# PhatStats_Slim_Enclosure_ESP_Lolin32_LIT.net
KiCad netlist of a schematic drawn in EAGLE
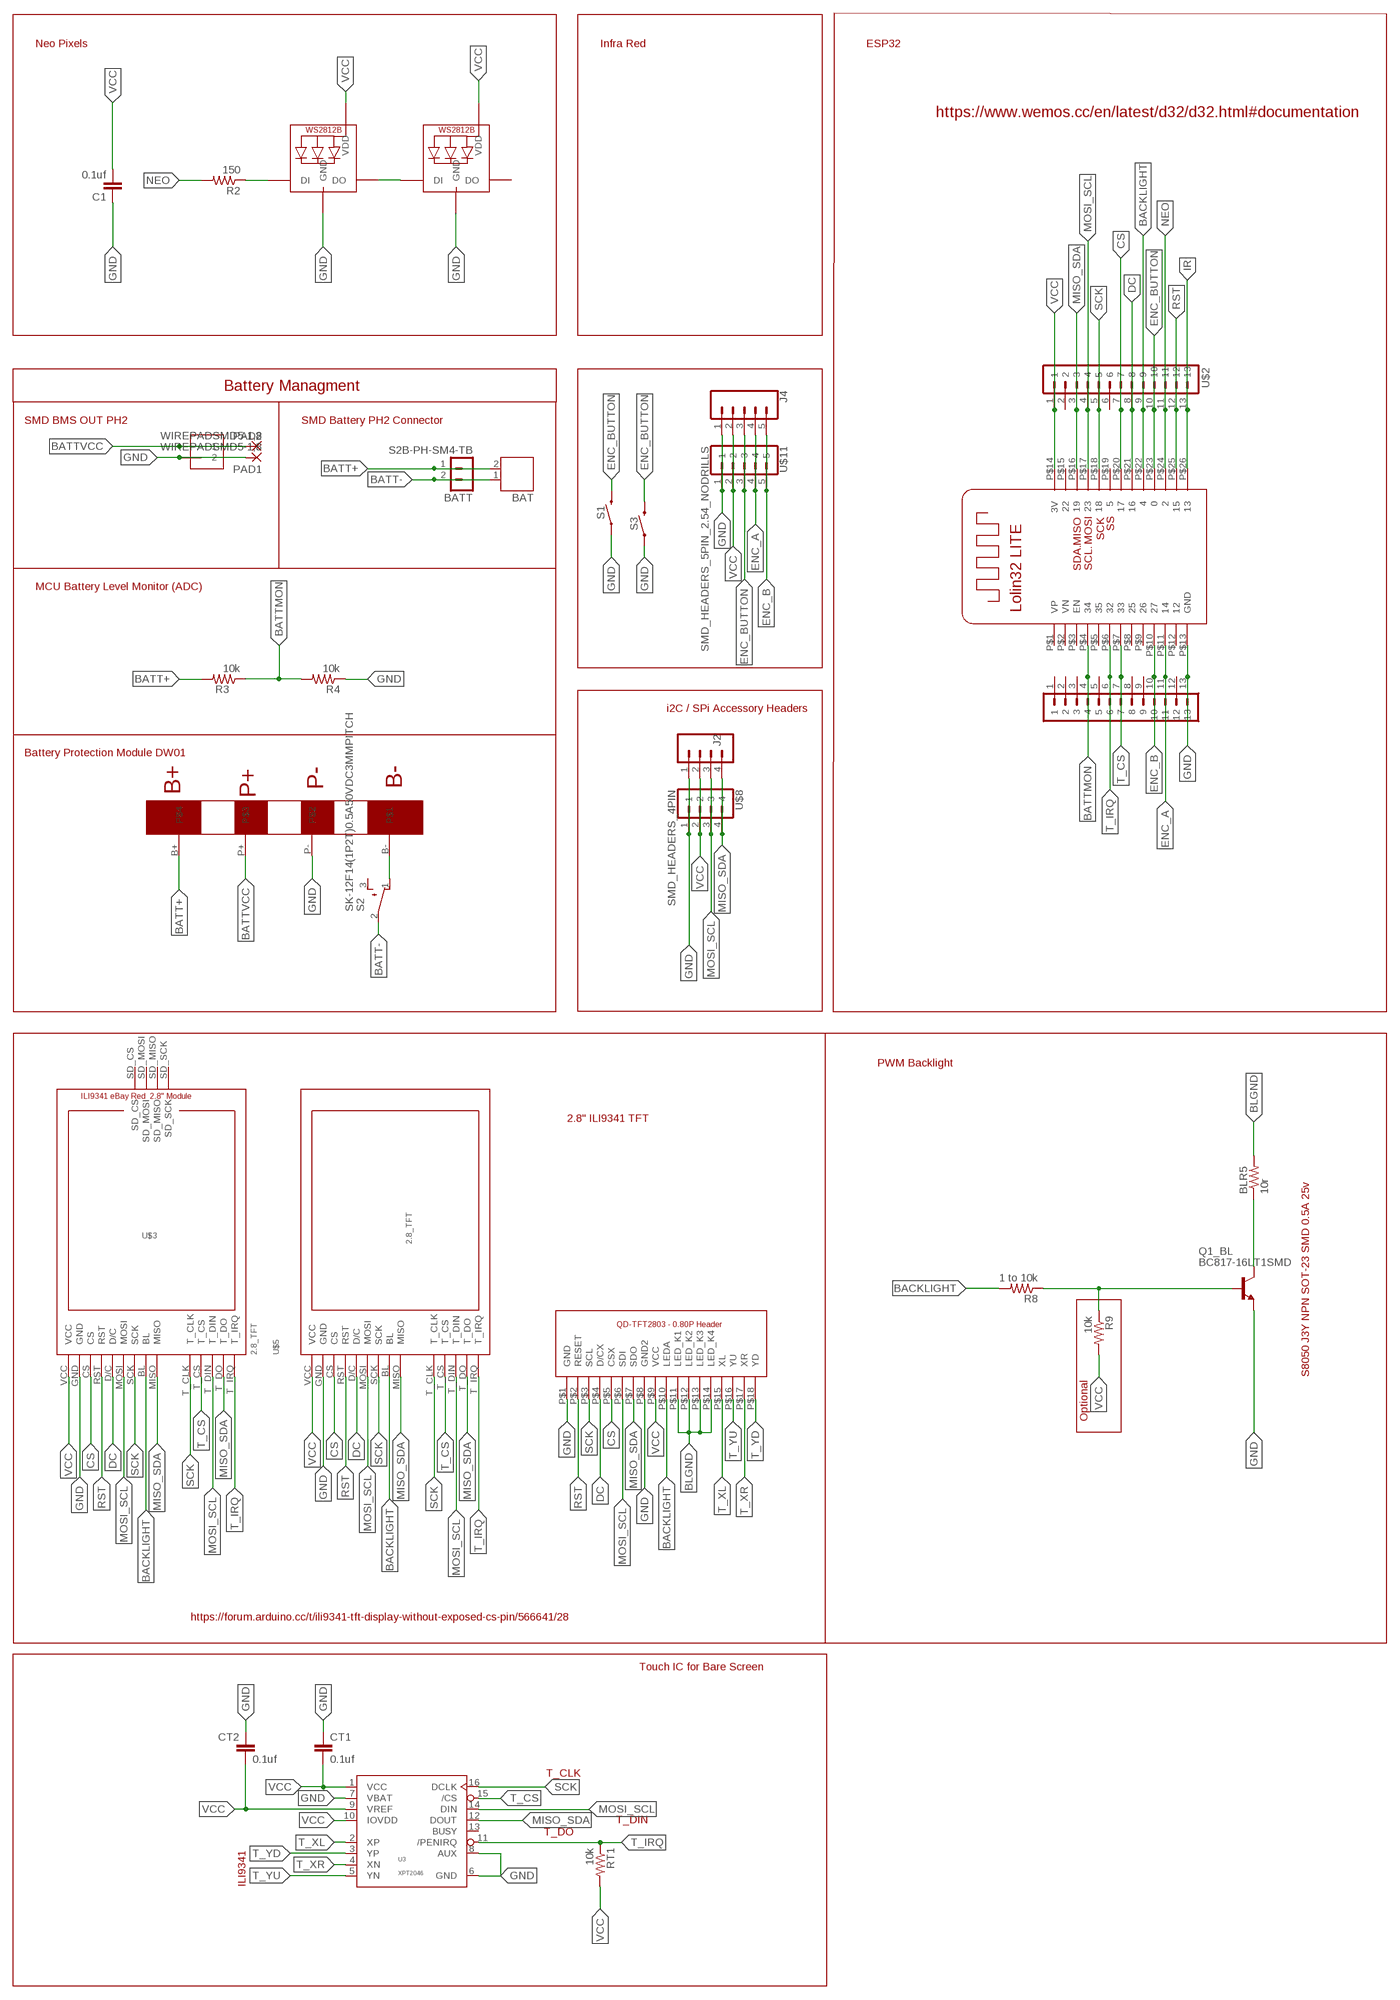
[diagram p0: schematic, sheet 1]

(export (version "E")
  (design (tool "Eeschema 10.0.6"))
  (components
    (comp (ref "0")
      (value "ILI9341-2.8")
      (footprint "eagle-import:ILI9341-2.8")
      (libsource (lib "eagle-import") (part "ILI9341-2.8"))
    )
    (comp (ref "BAT")
      (value "JST-PH2")
      (footprint "eagle-import:JST-PH2")
      (libsource (lib "eagle-import") (part "JST-PH2"))
    )
    (comp (ref "BATT")
      (value "S2B-PH-SM4-TB")
      (footprint "eagle-import:S2B-PH-SM4-TB")
      (libsource (lib "eagle-import") (part "S2B-PH-SM4-TB"))
    )
    (comp (ref "BLR5")
      (value "10r")
      (footprint "eagle-import:M1206")
      (libsource (lib "eagle-import") (part "R-US_M1206"))
    )
    (comp (ref "C1")
      (value "0.1uf")
      (footprint "eagle-import:C1206")
      (libsource (lib "eagle-import") (part "C-EUC1206"))
    )
    (comp (ref "CT1")
      (value "0.1uf")
      (footprint "eagle-import:C1206")
      (libsource (lib "eagle-import") (part "C-EUC1206"))
    )
    (comp (ref "CT2")
      (value "0.1uf")
      (footprint "eagle-import:C1206")
      (libsource (lib "eagle-import") (part "C-EUC1206"))
    )
    (comp (ref "DW01-BMS")
      (value "DW01BATTERYPROT")
      (footprint "eagle-import:DW01BATTERYPROT")
      (libsource (lib "eagle-import") (part "DW01BATTERYPROT"))
    )
    (comp (ref "J1")
      (value "1X2-3.5MM")
      (footprint "eagle-import:1X2-3.5MM")
      (libsource (lib "eagle-import") (part "1X2-3.5MM"))
    )
    (comp (ref "J2")
      (value "CONN_04PTH")
      (footprint "eagle-import:1X04")
      (libsource (lib "eagle-import") (part "CONN_04PTH"))
    )
    (comp (ref "J4")
      (value "CONN_05")
      (footprint "eagle-import:1X05")
      (libsource (lib "eagle-import") (part "CONN_05"))
    )
    (comp (ref "NEO0")
      (value "WS2812B5050")
      (footprint "eagle-import:WS2812B")
      (libsource (lib "eagle-import") (part "WS2812B5050"))
    )
    (comp (ref "NEO1")
      (value "WS2812B5050")
      (footprint "eagle-import:WS2812B")
      (libsource (lib "eagle-import") (part "WS2812B5050"))
    )
    (comp (ref "PAD1")
      (value "WIREPADSMD5-1,8")
      (footprint "eagle-import:5-1,8")
      (libsource (lib "eagle-import") (part "WIREPADSMD5-1,8"))
    )
    (comp (ref "PAD2")
      (value "WIREPADSMD5-1,8")
      (footprint "eagle-import:5-1,8")
      (libsource (lib "eagle-import") (part "WIREPADSMD5-1,8"))
    )
    (comp (ref "Q1_BL")
      (value "BC817-16LT1SMD")
      (footprint "eagle-import:SOT23-BEC")
      (libsource (lib "eagle-import") (part "BC817SMD-16LT1"))
    )
    (comp (ref "R2")
      (value "150")
      (footprint "eagle-import:M1206")
      (libsource (lib "eagle-import") (part "R-US_M1206"))
    )
    (comp (ref "R3")
      (value "10k")
      (footprint "eagle-import:M1206")
      (libsource (lib "eagle-import") (part "R-US_M1206"))
    )
    (comp (ref "R4")
      (value "10k")
      (footprint "eagle-import:M1206")
      (libsource (lib "eagle-import") (part "R-US_M1206"))
    )
    (comp (ref "R8")
      (value "1 to 10k")
      (footprint "eagle-import:M1206")
      (libsource (lib "eagle-import") (part "R-US_M1206"))
    )
    (comp (ref "R9")
      (value "10k")
      (footprint "eagle-import:M1206")
      (libsource (lib "eagle-import") (part "R-US_M1206"))
    )
    (comp (ref "RT1")
      (value "10k")
      (footprint "eagle-import:M1206")
      (libsource (lib "eagle-import") (part "R-US_M1206"))
    )
    (comp (ref "S1")
      (value "MOMENTARY-SWITCH-SPST-PTH-6.0MM")
      (footprint "eagle-import:TACTILE_SWITCH_PTH_6.0MM")
      (libsource (lib "eagle-import") (part "MOMENTARY-SWITCH-SPST-PTH-6.0MM"))
    )
    (comp (ref "S2")
      (value "SK-12F14(1P2T)0.5A50VDC3MMPITCH")
      (footprint "eagle-import:SK-12F14(1P2T)0.5A50VDC3MMPITCH")
      (libsource (lib "eagle-import") (part "SK-12F14(1P2T)0.5A50VDC3MMPITCH"))
    )
    (comp (ref "S3")
      (value "MOMENTARY-SWITCH-SPST-SMD-6.2MM-TALL")
      (footprint "eagle-import:TACTILE_SWITCH_SMD_6.2MM_TALL")
      (libsource (lib "eagle-import") (part "MOMENTARY-SWITCH-SPST-SMD-6.2MM-TALL"))
    )
    (comp (ref "U$1")
      (value "SMD_HEADERS_13PIN_2.54_NODRILLS")
      (footprint "eagle-import:SMD_HEADERS_13PIN")
      (libsource (lib "eagle-import") (part "SMD_HEADERS_13PIN_2.54_NODRILLS"))
    )
    (comp (ref "U$2")
      (value "SMD_HEADERS_13PIN_2.54_NODRILLS")
      (footprint "eagle-import:SMD_HEADERS_13PIN")
      (libsource (lib "eagle-import") (part "SMD_HEADERS_13PIN_2.54_NODRILLS"))
    )
    (comp (ref "U$3")
      (value "2.8_TFT")
      (footprint "eagle-import:2.8_TFT")
      (libsource (lib "eagle-import") (part "2.8_TFT"))
    )
    (comp (ref "U$5")
      (value "2.8_TFT")
      (footprint "eagle-import:2.8_TFT")
      (libsource (lib "eagle-import") (part "TML_ili9341-2.8_tft-display_PinHeader only_2.8_TFT"))
    )
    (comp (ref "U$7")
      (value "TML_LOLIND32_LITE")
      (footprint "eagle-import:TML_LOLIND32_LITE")
      (libsource (lib "eagle-import") (part "TML_LOLIND32_LITE"))
    )
    (comp (ref "U$8")
      (value "SMD_HEADERS_4PIN")
      (footprint "eagle-import:SMD_HEADERS_4PIN")
      (libsource (lib "eagle-import") (part "SMD_HEADERS_4PIN"))
    )
    (comp (ref "U$11")
      (value "SMD_HEADERS_5PIN_2.54_NODRILLS")
      (footprint "eagle-import:SMD_HEADERS_5PIN")
      (libsource (lib "eagle-import") (part "SMD_HEADERS_5PIN_2.54_NODRILLS"))
    )
    (comp (ref "U3")
      (value "XPT2046")
      (footprint "eagle-import:TSSOP-16")
      (fields (field (name "MF") "Xptek"))
      (libsource (lib "eagle-import") (part "XPT2046"))
    )
  )
  (nets
    (net (code "1") (name "BACKLIGHT") (class "Default")
      (node (ref "0") (pin "P$10") (pinfunction "LEDA_P$10") (pintype "bidirectional"))
      (node (ref "R8") (pin "2") (pinfunction "2_2") (pintype "passive"))
      (node (ref "U$2") (pin "9") (pinfunction "9_9") (pintype "bidirectional"))
      (node (ref "U$3") (pin "BL") (pinfunction "BL_BL") (pintype "bidirectional"))
      (node (ref "U$5") (pin "BL") (pinfunction "BL_BL") (pintype "bidirectional"))
      (node (ref "U$7") (pin "P$22") (pinfunction "4_P$22") (pintype "bidirectional"))
    )
    (net (code "2") (name "BATT+") (class "Default")
      (node (ref "BAT") (pin "2") (pinfunction "2_2") (pintype "passive"))
      (node (ref "BATT") (pin "1") (pinfunction "1_1") (pintype "passive"))
      (node (ref "DW01-BMS") (pin "B+") (pinfunction "P$4_B+") (pintype "bidirectional"))
      (node (ref "R3") (pin "2") (pinfunction "2_2") (pintype "passive"))
    )
    (net (code "3") (name "BATT-") (class "Default")
      (node (ref "BAT") (pin "1") (pinfunction "1_1") (pintype "passive"))
      (node (ref "BATT") (pin "2") (pinfunction "2_2") (pintype "passive"))
      (node (ref "S2") (pin "2") (pinfunction "P_2") (pintype "passive"))
    )
    (net (code "4") (name "BATTMON") (class "Default")
      (node (ref "R3") (pin "1") (pinfunction "1_1") (pintype "passive"))
      (node (ref "R4") (pin "2") (pinfunction "2_2") (pintype "passive"))
      (node (ref "U$1") (pin "4") (pinfunction "4_4") (pintype "bidirectional"))
      (node (ref "U$7") (pin "P$4") (pinfunction "34_P$4") (pintype "bidirectional"))
    )
    (net (code "5") (name "BATTVCC") (class "Default")
      (node (ref "DW01-BMS") (pin "P+") (pinfunction "P$3_P+") (pintype "bidirectional"))
      (node (ref "J1") (pin "1") (pinfunction "1_1") (pintype "passive"))
      (node (ref "PAD2") (pin "1") (pinfunction "P_1") (pintype "passive"))
    )
    (net (code "6") (name "BLGND") (class "Default")
      (node (ref "0") (pin "P$11") (pinfunction "LED_K1_P$11") (pintype "bidirectional"))
      (node (ref "0") (pin "P$12") (pinfunction "LED_K2_P$12") (pintype "bidirectional"))
      (node (ref "0") (pin "P$13") (pinfunction "LED_K3_P$13") (pintype "bidirectional"))
      (node (ref "0") (pin "P$14") (pinfunction "LED_K4_P$14") (pintype "bidirectional"))
      (node (ref "BLR5") (pin "2") (pinfunction "2_2") (pintype "passive"))
    )
    (net (code "7") (name "CS") (class "Default")
      (node (ref "0") (pin "P$5") (pinfunction "CSX_P$5") (pintype "bidirectional"))
      (node (ref "U$2") (pin "7") (pinfunction "7_7") (pintype "bidirectional"))
      (node (ref "U$3") (pin "CS") (pinfunction "CS_CS") (pintype "bidirectional"))
      (node (ref "U$5") (pin "CS") (pinfunction "CS_CS") (pintype "bidirectional"))
      (node (ref "U$7") (pin "P$20") (pinfunction "17_P$20") (pintype "bidirectional"))
    )
    (net (code "8") (name "DC") (class "Default")
      (node (ref "0") (pin "P$4") (pinfunction "D/CX_P$4") (pintype "bidirectional"))
      (node (ref "U$2") (pin "8") (pinfunction "8_8") (pintype "bidirectional"))
      (node (ref "U$3") (pin "D/C") (pinfunction "D/C_D/C") (pintype "bidirectional"))
      (node (ref "U$5") (pin "D/C") (pinfunction "D/C_D/C") (pintype "bidirectional"))
      (node (ref "U$7") (pin "P$21") (pinfunction "16_P$21") (pintype "bidirectional"))
    )
    (net (code "9") (name "ENC_A") (class "Default")
      (node (ref "J4") (pin "4") (pinfunction "4_4") (pintype "passive"))
      (node (ref "U$1") (pin "11") (pinfunction "11_11") (pintype "bidirectional"))
      (node (ref "U$11") (pin "4") (pinfunction "4_4") (pintype "passive"))
      (node (ref "U$7") (pin "P$11") (pinfunction "14_P$11") (pintype "bidirectional"))
    )
    (net (code "10") (name "ENC_B") (class "Default")
      (node (ref "J4") (pin "5") (pinfunction "5_5") (pintype "passive"))
      (node (ref "U$1") (pin "10") (pinfunction "10_10") (pintype "bidirectional"))
      (node (ref "U$11") (pin "5") (pinfunction "5_5") (pintype "passive"))
      (node (ref "U$7") (pin "P$10") (pinfunction "27_P$10") (pintype "bidirectional"))
    )
    (net (code "11") (name "ENC_BUTTON") (class "Default")
      (node (ref "J4") (pin "3") (pinfunction "3_3") (pintype "passive"))
      (node (ref "S1") (pin "3") (pinfunction "2_3") (pintype "passive"))
      (node (ref "S3") (pin "B2") (pinfunction "2_B2") (pintype "passive"))
      (node (ref "U$11") (pin "3") (pinfunction "3_3") (pintype "passive"))
      (node (ref "U$2") (pin "10") (pinfunction "10_10") (pintype "bidirectional"))
      (node (ref "U$7") (pin "P$23") (pinfunction "0_P$23") (pintype "bidirectional"))
    )
    (net (code "12") (name "GND") (class "Default")
      (node (ref "0") (pin "P$1") (pinfunction "GND_P$1") (pintype "bidirectional"))
      (node (ref "0") (pin "P$8") (pinfunction "GND2_P$8") (pintype "bidirectional"))
      (node (ref "C1") (pin "1") (pinfunction "1_1") (pintype "passive"))
      (node (ref "CT1") (pin "1") (pinfunction "1_1") (pintype "passive"))
      (node (ref "CT2") (pin "1") (pinfunction "1_1") (pintype "passive"))
      (node (ref "DW01-BMS") (pin "P-") (pinfunction "P$2_P-") (pintype "bidirectional"))
      (node (ref "J1") (pin "2") (pinfunction "2_2") (pintype "passive"))
      (node (ref "J2") (pin "1") (pinfunction "1_1") (pintype "passive"))
      (node (ref "J4") (pin "1") (pinfunction "1_1") (pintype "passive"))
      (node (ref "NEO0") (pin "3-GND") (pinfunction "GND_3-GND") (pintype "power_in"))
      (node (ref "NEO1") (pin "3-GND") (pinfunction "GND_3-GND") (pintype "power_in"))
      (node (ref "PAD1") (pin "1") (pinfunction "P_1") (pintype "passive"))
      (node (ref "Q1_BL") (pin "E") (pinfunction "E_E") (pintype "passive"))
      (node (ref "R4") (pin "1") (pinfunction "1_1") (pintype "passive"))
      (node (ref "S1") (pin "1") (pinfunction "1_1") (pintype "passive"))
      (node (ref "S3") (pin "A2") (pinfunction "1_A2") (pintype "passive"))
      (node (ref "U$1") (pin "13") (pinfunction "13_13") (pintype "bidirectional"))
      (node (ref "U$11") (pin "1") (pinfunction "1_1") (pintype "passive"))
      (node (ref "U$3") (pin "GND") (pinfunction "GND_GND") (pintype "bidirectional"))
      (node (ref "U$5") (pin "GND") (pinfunction "GND_GND") (pintype "bidirectional"))
      (node (ref "U$7") (pin "P$13") (pinfunction "GND_P$13") (pintype "input"))
      (node (ref "U$8") (pin "1") (pinfunction "1_1") (pintype "passive"))
      (node (ref "U3") (pin "6") (pinfunction "GND_6") (pintype "power_in"))
      (node (ref "U3") (pin "7") (pinfunction "VBAT_7") (pintype "input"))
      (node (ref "U3") (pin "8") (pinfunction "AUX_8") (pintype "input"))
    )
    (net (code "13") (name "IR") (class "Default")
      (node (ref "U$2") (pin "13") (pinfunction "13_13") (pintype "bidirectional"))
      (node (ref "U$7") (pin "P$26") (pinfunction "13_P$26") (pintype "bidirectional"))
    )
    (net (code "14") (name "MISO_SDA") (class "Default")
      (node (ref "0") (pin "P$7") (pinfunction "SDO_P$7") (pintype "bidirectional"))
      (node (ref "J2") (pin "4") (pinfunction "4_4") (pintype "passive"))
      (node (ref "U$2") (pin "3") (pinfunction "3_3") (pintype "bidirectional"))
      (node (ref "U$3") (pin "MISO") (pinfunction "MISO_MISO") (pintype "bidirectional"))
      (node (ref "U$3") (pin "T_DO") (pinfunction "T_DO_T_DO") (pintype "bidirectional"))
      (node (ref "U$5") (pin "MISO") (pinfunction "MISO_MISO") (pintype "bidirectional"))
      (node (ref "U$5") (pin "T_DO") (pinfunction "T_DO_T_DO") (pintype "bidirectional"))
      (node (ref "U$7") (pin "P$16") (pinfunction "19_P$16") (pintype "bidirectional"))
      (node (ref "U$8") (pin "4") (pinfunction "4_4") (pintype "passive"))
      (node (ref "U3") (pin "12") (pinfunction "DOUT_12") (pintype "output"))
    )
    (net (code "15") (name "MOSI_SCL") (class "Default")
      (node (ref "0") (pin "P$6") (pinfunction "SDI_P$6") (pintype "bidirectional"))
      (node (ref "J2") (pin "3") (pinfunction "3_3") (pintype "passive"))
      (node (ref "U$2") (pin "4") (pinfunction "4_4") (pintype "bidirectional"))
      (node (ref "U$3") (pin "MOSI") (pinfunction "MOSI_MOSI") (pintype "bidirectional"))
      (node (ref "U$3") (pin "T_DIN") (pinfunction "T_DIN_T_DIN") (pintype "bidirectional"))
      (node (ref "U$5") (pin "MOSI") (pinfunction "MOSI_MOSI") (pintype "bidirectional"))
      (node (ref "U$5") (pin "T_DIN") (pinfunction "T_DIN_T_DIN") (pintype "bidirectional"))
      (node (ref "U$7") (pin "P$17") (pinfunction "23_P$17") (pintype "bidirectional"))
      (node (ref "U$8") (pin "3") (pinfunction "3_3") (pintype "passive"))
      (node (ref "U3") (pin "14") (pinfunction "DIN_14") (pintype "input"))
    )
    (net (code "16") (name "NEO") (class "Default")
      (node (ref "R2") (pin "2") (pinfunction "2_2") (pintype "passive"))
      (node (ref "U$2") (pin "11") (pinfunction "11_11") (pintype "bidirectional"))
      (node (ref "U$7") (pin "P$24") (pinfunction "2_P$24") (pintype "bidirectional"))
    )
    (net (code "17") (name "Net-(BLR5-Pad1)") (class "Default")
      (node (ref "BLR5") (pin "1") (pinfunction "1_1") (pintype "passive"))
      (node (ref "Q1_BL") (pin "C") (pinfunction "C_C") (pintype "passive"))
    )
    (net (code "18") (name "Net-(DW01-BMS-P$1)") (class "Default")
      (node (ref "DW01-BMS") (pin "B-") (pinfunction "P$1_B-") (pintype "bidirectional"))
      (node (ref "S2") (pin "1") (pinfunction "O_1") (pintype "passive"))
    )
    (net (code "19") (name "Net-(NEO0-DI)") (class "Default")
      (node (ref "NEO0") (pin "4-DIN") (pinfunction "DI_4-DIN") (pintype "input"))
      (node (ref "R2") (pin "1") (pinfunction "1_1") (pintype "passive"))
    )
    (net (code "20") (name "Net-(NEO0-DO)") (class "Default")
      (node (ref "NEO0") (pin "2-DOUT") (pinfunction "DO_2-DOUT") (pintype "output"))
      (node (ref "NEO1") (pin "4-DIN") (pinfunction "DI_4-DIN") (pintype "input"))
    )
    (net (code "21") (name "Net-(Q1_BL-PadB)") (class "Default")
      (node (ref "Q1_BL") (pin "B") (pinfunction "B_B") (pintype "passive"))
      (node (ref "R8") (pin "1") (pinfunction "1_1") (pintype "passive"))
      (node (ref "R9") (pin "1") (pinfunction "1_1") (pintype "passive"))
    )
    (net (code "22") (name "RST") (class "Default")
      (node (ref "0") (pin "P$2") (pinfunction "RESET_P$2") (pintype "bidirectional"))
      (node (ref "U$2") (pin "12") (pinfunction "12_12") (pintype "bidirectional"))
      (node (ref "U$3") (pin "RST") (pinfunction "RST_RST") (pintype "bidirectional"))
      (node (ref "U$5") (pin "RST") (pinfunction "RST_RST") (pintype "bidirectional"))
      (node (ref "U$7") (pin "P$25") (pinfunction "15_P$25") (pintype "bidirectional"))
    )
    (net (code "23") (name "SCK") (class "Default")
      (node (ref "0") (pin "P$3") (pinfunction "SCL_P$3") (pintype "bidirectional"))
      (node (ref "U$2") (pin "5") (pinfunction "5_5") (pintype "bidirectional"))
      (node (ref "U$3") (pin "SCK") (pinfunction "SCK_SCK") (pintype "bidirectional"))
      (node (ref "U$3") (pin "T_CLK") (pinfunction "T_CLK_T_CLK") (pintype "bidirectional"))
      (node (ref "U$5") (pin "SCK") (pinfunction "SCK_SCK") (pintype "bidirectional"))
      (node (ref "U$5") (pin "T_CLK") (pinfunction "T_CLK_T_CLK") (pintype "bidirectional"))
      (node (ref "U$7") (pin "P$18") (pinfunction "18_P$18") (pintype "bidirectional"))
      (node (ref "U3") (pin "16") (pinfunction "DCLK_16") (pintype "input"))
    )
    (net (code "24") (name "T_CS") (class "Default")
      (node (ref "U$1") (pin "7") (pinfunction "7_7") (pintype "bidirectional"))
      (node (ref "U$3") (pin "T_CS") (pinfunction "T_CS_T_CS") (pintype "bidirectional"))
      (node (ref "U$5") (pin "T_CS") (pinfunction "T_CS_T_CS") (pintype "bidirectional"))
      (node (ref "U$7") (pin "P$7") (pinfunction "33_P$7") (pintype "bidirectional"))
      (node (ref "U3") (pin "15") (pinfunction "/CS_15") (pintype "input"))
    )
    (net (code "25") (name "T_IRQ") (class "Default")
      (node (ref "RT1") (pin "1") (pinfunction "1_1") (pintype "passive"))
      (node (ref "U$1") (pin "6") (pinfunction "6_6") (pintype "bidirectional"))
      (node (ref "U$3") (pin "T_IRQ") (pinfunction "T_IRQ_T_IRQ") (pintype "bidirectional"))
      (node (ref "U$5") (pin "T_IRQ") (pinfunction "T_IRQ_T_IRQ") (pintype "bidirectional"))
      (node (ref "U$7") (pin "P$6") (pinfunction "32_P$6") (pintype "bidirectional"))
      (node (ref "U3") (pin "11") (pinfunction "/PENIRQ_11") (pintype "output"))
    )
    (net (code "26") (name "T_XL") (class "Default")
      (node (ref "0") (pin "P$15") (pinfunction "XL_P$15") (pintype "bidirectional"))
      (node (ref "U3") (pin "2") (pinfunction "XP_2") (pintype "input"))
    )
    (net (code "27") (name "T_XR") (class "Default")
      (node (ref "0") (pin "P$17") (pinfunction "XR_P$17") (pintype "bidirectional"))
      (node (ref "U3") (pin "4") (pinfunction "XN_4") (pintype "input"))
    )
    (net (code "28") (name "T_YD") (class "Default")
      (node (ref "0") (pin "P$18") (pinfunction "YD_P$18") (pintype "bidirectional"))
      (node (ref "U3") (pin "3") (pinfunction "YP_3") (pintype "input"))
    )
    (net (code "29") (name "T_YU") (class "Default")
      (node (ref "0") (pin "P$16") (pinfunction "YU_P$16") (pintype "bidirectional"))
      (node (ref "U3") (pin "5") (pinfunction "YN_5") (pintype "input"))
    )
    (net (code "30") (name "VCC") (class "Default")
      (node (ref "0") (pin "P$9") (pinfunction "VCC_P$9") (pintype "bidirectional"))
      (node (ref "C1") (pin "2") (pinfunction "2_2") (pintype "passive"))
      (node (ref "CT1") (pin "2") (pinfunction "2_2") (pintype "passive"))
      (node (ref "CT2") (pin "2") (pinfunction "2_2") (pintype "passive"))
      (node (ref "J2") (pin "2") (pinfunction "2_2") (pintype "passive"))
      (node (ref "J4") (pin "2") (pinfunction "2_2") (pintype "passive"))
      (node (ref "NEO0") (pin "1-VDD") (pinfunction "VDD_1-VDD") (pintype "power_in"))
      (node (ref "NEO1") (pin "1-VDD") (pinfunction "VDD_1-VDD") (pintype "power_in"))
      (node (ref "R9") (pin "2") (pinfunction "2_2") (pintype "passive"))
      (node (ref "RT1") (pin "2") (pinfunction "2_2") (pintype "passive"))
      (node (ref "U$11") (pin "2") (pinfunction "2_2") (pintype "passive"))
      (node (ref "U$2") (pin "1") (pinfunction "1_1") (pintype "bidirectional"))
      (node (ref "U$3") (pin "VCC") (pinfunction "VCC_VCC") (pintype "bidirectional"))
      (node (ref "U$5") (pin "VCC") (pinfunction "VCC_VCC") (pintype "bidirectional"))
      (node (ref "U$7") (pin "P$14") (pinfunction "3V_P$14") (pintype "input"))
      (node (ref "U$8") (pin "2") (pinfunction "2_2") (pintype "passive"))
      (node (ref "U3") (pin "1") (pinfunction "VCC_1") (pintype "power_in"))
      (node (ref "U3") (pin "10") (pinfunction "IOVDD_10") (pintype "power_in"))
      (node (ref "U3") (pin "9") (pinfunction "VREF_9") (pintype "input"))
    )
    (net (code "31") (name "unconnected-(NEO1-DO-Pad2-DOUT)") (class "Default")
      (node (ref "NEO1") (pin "2-DOUT") (pinfunction "DO_2-DOUT") (pintype "output"))
    )
    (net (code "32") (name "unconnected-(S2-S-Pad3)") (class "Default")
      (node (ref "S2") (pin "3") (pinfunction "S_3") (pintype "passive"))
    )
    (net (code "33") (name "unconnected-(U$1-Pad1)") (class "Default")
      (node (ref "U$1") (pin "1") (pinfunction "1_1") (pintype "bidirectional"))
    )
    (net (code "34") (name "unconnected-(U$1-Pad2)") (class "Default")
      (node (ref "U$1") (pin "2") (pinfunction "2_2") (pintype "bidirectional"))
    )
    (net (code "35") (name "unconnected-(U$1-Pad3)") (class "Default")
      (node (ref "U$1") (pin "3") (pinfunction "3_3") (pintype "bidirectional"))
    )
    (net (code "36") (name "unconnected-(U$1-Pad5)") (class "Default")
      (node (ref "U$1") (pin "5") (pinfunction "5_5") (pintype "bidirectional"))
    )
    (net (code "37") (name "unconnected-(U$1-Pad8)") (class "Default")
      (node (ref "U$1") (pin "8") (pinfunction "8_8") (pintype "bidirectional"))
    )
    (net (code "38") (name "unconnected-(U$1-Pad9)") (class "Default")
      (node (ref "U$1") (pin "9") (pinfunction "9_9") (pintype "bidirectional"))
    )
    (net (code "39") (name "unconnected-(U$1-Pad12)") (class "Default")
      (node (ref "U$1") (pin "12") (pinfunction "12_12") (pintype "bidirectional"))
    )
    (net (code "40") (name "unconnected-(U$2-Pad2)") (class "Default")
      (node (ref "U$2") (pin "2") (pinfunction "2_2") (pintype "bidirectional"))
    )
    (net (code "41") (name "unconnected-(U$2-Pad6)") (class "Default")
      (node (ref "U$2") (pin "6") (pinfunction "6_6") (pintype "bidirectional"))
    )
    (net (code "42") (name "unconnected-(U$3-PadSD_CS)") (class "Default")
      (node (ref "U$3") (pin "SD_CS") (pinfunction "SD_CS_SD_CS") (pintype "bidirectional"))
    )
    (net (code "43") (name "unconnected-(U$3-PadSD_MISO)") (class "Default")
      (node (ref "U$3") (pin "SD_MISO") (pinfunction "SD_MISO_SD_MISO") (pintype "bidirectional"))
    )
    (net (code "44") (name "unconnected-(U$3-PadSD_MOSI)") (class "Default")
      (node (ref "U$3") (pin "SD_MOSI") (pinfunction "SD_MOSI_SD_MOSI") (pintype "bidirectional"))
    )
    (net (code "45") (name "unconnected-(U$3-PadSD_SCK)") (class "Default")
      (node (ref "U$3") (pin "SD_SCK") (pinfunction "SD_SCK_SD_SCK") (pintype "bidirectional"))
    )
    (net (code "46") (name "unconnected-(U$7-5-PadP$19)") (class "Default")
      (node (ref "U$7") (pin "P$19") (pinfunction "5_P$19") (pintype "bidirectional"))
    )
    (net (code "47") (name "unconnected-(U$7-12-PadP$12)") (class "Default")
      (node (ref "U$7") (pin "P$12") (pinfunction "12_P$12") (pintype "bidirectional"))
    )
    (net (code "48") (name "unconnected-(U$7-22-PadP$15)") (class "Default")
      (node (ref "U$7") (pin "P$15") (pinfunction "22_P$15") (pintype "bidirectional"))
    )
    (net (code "49") (name "unconnected-(U$7-25-PadP$8)") (class "Default")
      (node (ref "U$7") (pin "P$8") (pinfunction "25_P$8") (pintype "bidirectional"))
    )
    (net (code "50") (name "unconnected-(U$7-26-PadP$9)") (class "Default")
      (node (ref "U$7") (pin "P$9") (pinfunction "26_P$9") (pintype "bidirectional"))
    )
    (net (code "51") (name "unconnected-(U$7-35-PadP$5)") (class "Default")
      (node (ref "U$7") (pin "P$5") (pinfunction "35_P$5") (pintype "bidirectional"))
    )
    (net (code "52") (name "unconnected-(U$7-EN-PadP$3)") (class "Default")
      (node (ref "U$7") (pin "P$3") (pinfunction "EN_P$3") (pintype "bidirectional"))
    )
    (net (code "53") (name "unconnected-(U$7-VN-PadP$2)") (class "Default")
      (node (ref "U$7") (pin "P$2") (pinfunction "VN_P$2") (pintype "bidirectional"))
    )
    (net (code "54") (name "unconnected-(U$7-VP-PadP$1)") (class "Default")
      (node (ref "U$7") (pin "P$1") (pinfunction "VP_P$1") (pintype "bidirectional"))
    )
    (net (code "55") (name "unconnected-(U3-BUSY-Pad13)") (class "Default")
      (node (ref "U3") (pin "13") (pinfunction "BUSY_13") (pintype "output"))
    )
  )
)
